# Power.net
KiCad netlist of a schematic drawn in Altium Designer
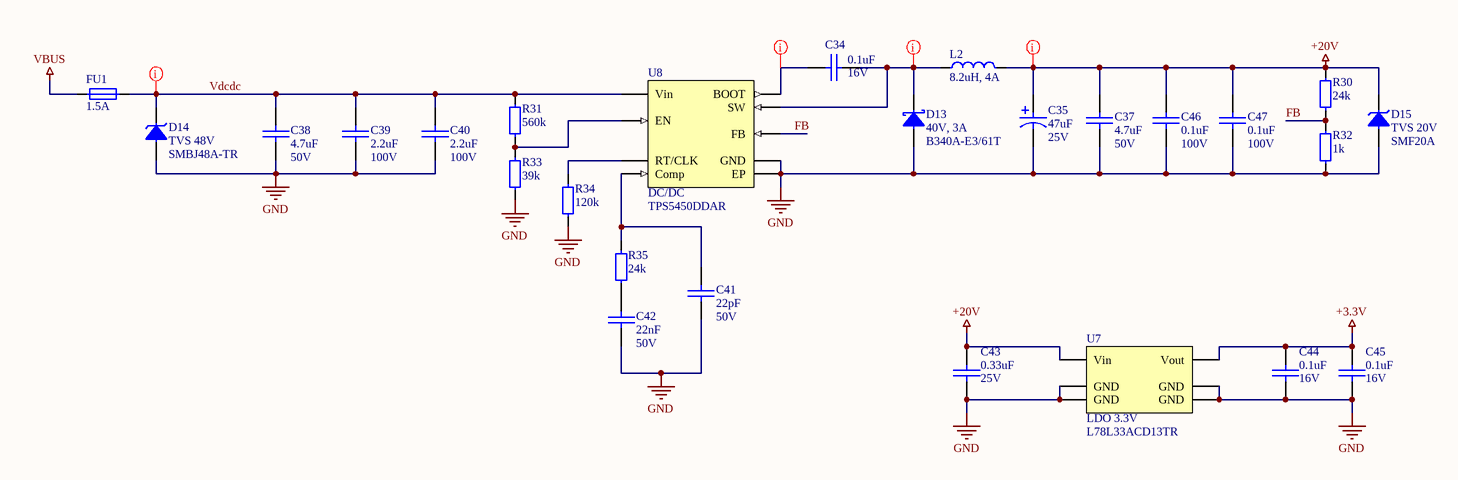
[diagram p0: Power.SchDoc]

(export (version "E")
  (design (tool "Eeschema 10.0.6"))
  (components
    (comp (ref "C34")
      (value "0.1uF")
      (footprint "0603 Capicator")
      (description "0.1uF X7R 16V 10% 0603")
      (fields
        (field (name "MANUFACTURER") "Murata Manufacturing")
        (field (name "PART NUMBER") "GRM188R71C104KA01D")
        (field (name "VOLTAGE") "16V")
      )
      (libsource (lib "Karen_Components") (part "Cap 0.1uF (0603)"))
    )
    (comp (ref "C35")
      (value "47uF")
      (footprint "Bar Cap 6.3x7.7")
      (description "ECAP SMD,  25V, 105°C, 20%")
      (fields
        (field (name "PART NUMBER") "JCK1E470M063054")
        (field (name "MANUFACTURER") "JB")
        (field (name "VOLTAGE") "25V")
      )
      (libsource (lib "Karen_Components") (part "Cap Pol 47uF (25V)"))
    )
    (comp (ref "C37")
      (value "4.7uF")
      (footprint "1206 Capacitor")
      (description "4.7uF X7R 10% 50V 1206")
      (fields
        (field (name "MANUFACTURER") "Murata Manufacturing")
        (field (name "PART NUMBER") "GRM31CR71H475KA12L")
        (field (name "VOLTAGE") "50V")
      )
      (libsource (lib "Karen_Components") (part "Cap 4.7uF (1206)"))
    )
    (comp (ref "C38")
      (value "4.7uF")
      (footprint "1206 Capacitor")
      (description "4.7uF X7R 10% 50V 1206")
      (fields
        (field (name "MANUFACTURER") "Murata Manufacturing")
        (field (name "PART NUMBER") "GRM31CR71H475KA12L")
        (field (name "VOLTAGE") "50V")
      )
      (libsource (lib "Karen_Components") (part "Cap 4.7uF (1206)"))
    )
    (comp (ref "C39")
      (value "2.2uF")
      (footprint "1206 Capacitor")
      (description "2.2uF X7R 10% 100V 1206")
      (fields
        (field (name "MANUFACTURER") "Murata Manufacturing")
        (field (name "PART NUMBER") "GRM31CR72A225KA73L")
        (field (name "VOLTAGE") "100V")
      )
      (libsource (lib "Karen_Components") (part "Cap 2.2uF (1206)"))
    )
    (comp (ref "C40")
      (value "2.2uF")
      (footprint "1206 Capacitor")
      (description "2.2uF X7R 10% 100V 1206")
      (fields
        (field (name "MANUFACTURER") "Murata Manufacturing")
        (field (name "PART NUMBER") "GRM31CR72A225KA73L")
        (field (name "VOLTAGE") "100V")
      )
      (libsource (lib "Karen_Components") (part "Cap 2.2uF (1206)"))
    )
    (comp (ref "C41")
      (value "22pF")
      (footprint "0603 Capicator")
      (description "22pF NP0 50V 5% 0603")
      (fields
        (field (name "MANUFACTURER") "Taiwan")
        (field (name "PART NUMBER") "MLCC22pFNPO50V5%0603")
        (field (name "VOLTAGE") "50V")
      )
      (libsource (lib "Karen_Components") (part "Cap 22pF (0603)"))
    )
    (comp (ref "C42")
      (value "22nF")
      (footprint "0603 Capicator")
      (description "22nF X7R 50V 10% 0603")
      (fields
        (field (name "MANUFACTURER") "Murata Manufacturing")
        (field (name "PART NUMBER") "GRM188R71H223KA01D")
        (field (name "VOLTAGE") "50V")
      )
      (libsource (lib "Karen_Components") (part "Cap 22nF (0603)"))
    )
    (comp (ref "C43")
      (value "0.33uF")
      (footprint "0805 Capicator")
      (description "0.33uF X7R 25V 10% 0805")
      (fields
        (field (name "MANUFACTURER") "Murata Manufacturing")
        (field (name "PART NUMBER") "GRM21BR71E334KA01L")
        (field (name "VOLTAGE") "25V")
      )
      (libsource (lib "Karen_Components") (part "Cap 0.33uF (0805)"))
    )
    (comp (ref "C44")
      (value "0.1uF")
      (footprint "0603 Capicator")
      (description "0.1uF X7R 16V 10% 0603")
      (fields
        (field (name "MANUFACTURER") "Murata Manufacturing")
        (field (name "PART NUMBER") "GRM188R71C104KA01D")
        (field (name "VOLTAGE") "16V")
      )
      (libsource (lib "Karen_Components") (part "Cap 0.1uF (0603)"))
    )
    (comp (ref "C45")
      (value "0.1uF")
      (footprint "0603 Capicator")
      (description "0.1uF X7R 16V 10% 0603")
      (fields
        (field (name "MANUFACTURER") "Murata Manufacturing")
        (field (name "PART NUMBER") "GRM188R71C104KA01D")
        (field (name "VOLTAGE") "16V")
      )
      (libsource (lib "Karen_Components") (part "Cap 0.1uF (0603)"))
    )
    (comp (ref "C46")
      (value "0.1uF")
      (footprint "1206 Capacitor")
      (description "0.1uF X7R 100V 10% 1206")
      (fields
        (field (name "MANUFACTURER") "Murata Manufacturing")
        (field (name "PART NUMBER") "GRM319R72A104KA01D")
        (field (name "VOLTAGE") "100V")
      )
      (libsource (lib "Karen_Components") (part "Cap 0.1uF (1206)"))
    )
    (comp (ref "C47")
      (value "0.1uF")
      (footprint "1206 Capacitor")
      (description "0.1uF X7R 100V 10% 1206")
      (fields
        (field (name "MANUFACTURER") "Murata Manufacturing")
        (field (name "PART NUMBER") "GRM319R72A104KA01D")
        (field (name "VOLTAGE") "100V")
      )
      (libsource (lib "Karen_Components") (part "Cap 0.1uF (1206)"))
    )
    (comp (ref "D13")
      (value "40V, 3A")
      (footprint "SMA")
      (description "Diode Schottky 3A 40V")
      (fields (field (name "MANUFACTURER") "Vishay") (field (name "PART NUMBER") "B340A-E3/61T"))
      (libsource (lib "Karen_Components") (part "Diode Schottky (SMA)"))
    )
    (comp (ref "D14")
      (value "TVS 48V")
      (footprint "SMB")
      (description "600W")
      (fields (field (name "MANUFACTURER") "STMicroelectronics") (field (name "PART NUMBER") "SMBJ48A-TR"))
      (libsource (lib "Karen_Components") (part "TVS Diode 48V [SMBJ]"))
    )
    (comp (ref "D15")
      (value "TVS 20V")
      (footprint "SOD-123FL")
      (description "200W")
      (fields
        (field (name "MANUFACTURER") "Yangzhou Yangjie Electronic Technology Co., Ltd.")
        (field (name "PART NUMBER") "SMF20A")
      )
      (libsource (lib "Karen_Components") (part "TVS Diode 20V [SMF]"))
    )
    (comp (ref "FU1")
      (value "1.5A")
      (footprint "1812 Fuse")
      (fields (field (name "PART NUMBER") "MF-MSMF150-2") (field (name "MANUFACTURER") "Bourns"))
      (libsource (lib "Karen_Components") (part "Fuse Resettable 1.5A"))
    )
    (comp (ref "L2")
      (value "8.2uH, 4A")
      (footprint "Inductor 6.9x6.5")
      (description "8.2 uH, 4А, 20%, 6.9х6.5х3mm")
      (fields (field (name "PART NUMBER") "IHLP2525CZER8R2M01") (field (name "MANUFACTURER") "Vishay"))
      (libsource (lib "Karen_Components") (part "Inductor 8.2uH (4A)"))
    )
    (comp (ref "R30")
      (value "24k")
      (footprint "0603 Resistor")
      (description "0.1W 0603 24k, 1%")
      (fields (field (name "PART NUMBER") "RC0603FR-0724KL") (field (name "MANUFACTURER") "Taiwan"))
      (libsource (lib "Karen_Components") (part "Res 24k (0603)"))
    )
    (comp (ref "R31")
      (value "560k")
      (footprint "0603 Resistor")
      (description "0.1W 0603 560k, 1%")
      (fields (field (name "PART NUMBER") "RC0603FR-07560KL") (field (name "MANUFACTURER") "Taiwan"))
      (libsource (lib "Karen_Components") (part "Res 560k (0603)"))
    )
    (comp (ref "R32")
      (value "1k")
      (footprint "0603 Resistor")
      (description "0.1W 0603 1k, 1%")
      (fields (field (name "PART NUMBER") "RC0603FR-071KL") (field (name "MANUFACTURER") "Taiwan"))
      (libsource (lib "Karen_Components") (part "Res 1k (0603)"))
    )
    (comp (ref "R33")
      (value "39k")
      (footprint "0603 Resistor")
      (description "0.1W 0603 39k, 1%")
      (fields (field (name "PART NUMBER") "RC0603FR-0739KL") (field (name "MANUFACTURER") "Taiwan"))
      (libsource (lib "Karen_Components") (part "Res 39k (0603)"))
    )
    (comp (ref "R34")
      (value "120k")
      (footprint "0603 Resistor")
      (description "0.1W 0603 120k, 1%")
      (fields (field (name "PART NUMBER") "RC0603FR-07120KL") (field (name "MANUFACTURER") "Taiwan"))
      (libsource (lib "Karen_Components") (part "Res 120k (0603)"))
    )
    (comp (ref "R35")
      (value "24k")
      (footprint "0603 Resistor")
      (description "0.1W 0603 24k, 1%")
      (fields (field (name "PART NUMBER") "RC0603FR-0724KL") (field (name "MANUFACTURER") "Taiwan"))
      (libsource (lib "Karen_Components") (part "Res 24k (0603)"))
    )
    (comp (ref "U7")
      (value "LDO 3.3V")
      (footprint "SOIC-8")
      (fields (field (name "MANUFACTURER") "STMicroelectronics") (field (name "PART NUMBER") "L78L33ACD13TR"))
      (libsource (lib "Karen_Components") (part "LDO 3.3V [L78]"))
    )
    (comp (ref "U8")
      (value "DC/DC")
      (footprint "HSOP-8")
      (fields (field (name "MANUFACTURER") "Texas Instruments") (field (name "PART NUMBER") "TPS5450DDAR"))
      (libsource (lib "Karen_Components") (part "DC/DC Controller [TPS5450DDAR]"))
    )
  )
  (nets
    (net (code "1") (name "+3.3V") (class "Default")
      (node (ref "C44") (pin "2") (pinfunction "2_2") (pintype "passive"))
      (node (ref "C45") (pin "2") (pinfunction "2_2") (pintype "passive"))
      (node (ref "U7") (pin "1") (pinfunction "Vout_1") (pintype "power_in"))
    )
    (net (code "2") (name "+20V") (class "Default")
      (node (ref "C35") (pin "2") (pinfunction "2_2") (pintype "passive"))
      (node (ref "C37") (pin "2") (pinfunction "2_2") (pintype "passive"))
      (node (ref "C43") (pin "2") (pinfunction "2_2") (pintype "passive"))
      (node (ref "C46") (pin "2") (pinfunction "2_2") (pintype "passive"))
      (node (ref "C47") (pin "2") (pinfunction "2_2") (pintype "passive"))
      (node (ref "D15") (pin "2") (pinfunction "2_2") (pintype "passive"))
      (node (ref "L2") (pin "2") (pinfunction "2_2") (pintype "passive"))
      (node (ref "R30") (pin "2") (pinfunction "2_2") (pintype "passive"))
      (node (ref "U7") (pin "8") (pinfunction "Vin_8") (pintype "power_in"))
    )
    (net (code "3") (name "/FB") (class "Default")
      (node (ref "R30") (pin "1") (pinfunction "1_1") (pintype "passive"))
      (node (ref "R32") (pin "2") (pinfunction "2_2") (pintype "passive"))
      (node (ref "U8") (pin "5") (pinfunction "FB_5") (pintype "input"))
    )
    (net (code "4") (name "/Vdcdc") (class "Default")
      (node (ref "C38") (pin "2") (pinfunction "2_2") (pintype "passive"))
      (node (ref "C39") (pin "2") (pinfunction "2_2") (pintype "passive"))
      (node (ref "C40") (pin "2") (pinfunction "2_2") (pintype "passive"))
      (node (ref "D14") (pin "2") (pinfunction "2_2") (pintype "passive"))
      (node (ref "FU1") (pin "2") (pinfunction "2_2") (pintype "passive"))
      (node (ref "R31") (pin "2") (pinfunction "2_2") (pintype "passive"))
      (node (ref "U8") (pin "2") (pinfunction "Vin_2") (pintype "power_in"))
    )
    (net (code "5") (name "GND") (class "Default")
      (node (ref "C35") (pin "1") (pinfunction "1_1") (pintype "passive"))
      (node (ref "C37") (pin "1") (pinfunction "1_1") (pintype "passive"))
      (node (ref "C38") (pin "1") (pinfunction "1_1") (pintype "passive"))
      (node (ref "C39") (pin "1") (pinfunction "1_1") (pintype "passive"))
      (node (ref "C40") (pin "1") (pinfunction "1_1") (pintype "passive"))
      (node (ref "C41") (pin "1") (pinfunction "1_1") (pintype "passive"))
      (node (ref "C42") (pin "1") (pinfunction "1_1") (pintype "passive"))
      (node (ref "C43") (pin "1") (pinfunction "1_1") (pintype "passive"))
      (node (ref "C44") (pin "1") (pinfunction "1_1") (pintype "passive"))
      (node (ref "C45") (pin "1") (pinfunction "1_1") (pintype "passive"))
      (node (ref "C46") (pin "1") (pinfunction "1_1") (pintype "passive"))
      (node (ref "C47") (pin "1") (pinfunction "1_1") (pintype "passive"))
      (node (ref "D13") (pin "1") (pinfunction "1_1") (pintype "passive"))
      (node (ref "D14") (pin "1") (pinfunction "1_1") (pintype "passive"))
      (node (ref "D15") (pin "1") (pinfunction "1_1") (pintype "passive"))
      (node (ref "R32") (pin "1") (pinfunction "1_1") (pintype "passive"))
      (node (ref "R33") (pin "1") (pinfunction "1_1") (pintype "passive"))
      (node (ref "R34") (pin "1") (pinfunction "1_1") (pintype "passive"))
      (node (ref "U7") (pin "2") (pinfunction "GND_2") (pintype "power_in"))
      (node (ref "U7") (pin "3") (pinfunction "GND_3") (pintype "power_in"))
      (node (ref "U7") (pin "6") (pinfunction "GND_6") (pintype "power_in"))
      (node (ref "U7") (pin "7") (pinfunction "GND_7") (pintype "power_in"))
      (node (ref "U8") (pin "7") (pinfunction "GND_7") (pintype "power_in"))
      (node (ref "U8") (pin "A") (pinfunction "EP_A") (pintype "power_in"))
    )
    (net (code "6") (name "Net-(C42-Pad2)") (class "Default")
      (node (ref "C42") (pin "2") (pinfunction "2_2") (pintype "passive"))
      (node (ref "R35") (pin "1") (pinfunction "1_1") (pintype "passive"))
    )
    (net (code "7") (name "Net-(U8-BOOT)") (class "Default")
      (node (ref "C34") (pin "1") (pinfunction "1_1") (pintype "passive"))
      (node (ref "U8") (pin "1") (pinfunction "BOOT_1") (pintype "output"))
    )
    (net (code "8") (name "Net-(U8-Comp)") (class "Default")
      (node (ref "C41") (pin "2") (pinfunction "2_2") (pintype "passive"))
      (node (ref "R35") (pin "2") (pinfunction "2_2") (pintype "passive"))
      (node (ref "U8") (pin "6") (pinfunction "Comp_6") (pintype "input"))
    )
    (net (code "9") (name "Net-(U8-EN)") (class "Default")
      (node (ref "R31") (pin "1") (pinfunction "1_1") (pintype "passive"))
      (node (ref "R33") (pin "2") (pinfunction "2_2") (pintype "passive"))
      (node (ref "U8") (pin "3") (pinfunction "EN_3") (pintype "input"))
    )
    (net (code "10") (name "Net-(U8-RT{slash}CLK)") (class "Default")
      (node (ref "R34") (pin "2") (pinfunction "2_2") (pintype "passive"))
      (node (ref "U8") (pin "4") (pinfunction "RT/CLK_4") (pintype "passive"))
    )
    (net (code "11") (name "Net-(U8-SW)") (class "Default")
      (node (ref "C34") (pin "2") (pinfunction "2_2") (pintype "passive"))
      (node (ref "D13") (pin "2") (pinfunction "2_2") (pintype "passive"))
      (node (ref "L2") (pin "1") (pinfunction "1_1") (pintype "passive"))
      (node (ref "U8") (pin "8") (pinfunction "SW_8") (pintype "input"))
    )
    (net (code "12") (name "VBUS") (class "Default")
      (node (ref "FU1") (pin "1") (pinfunction "1_1") (pintype "passive"))
    )
  )
)
